# remote_control.net
KiCad netlist of a schematic drawn in EAGLE
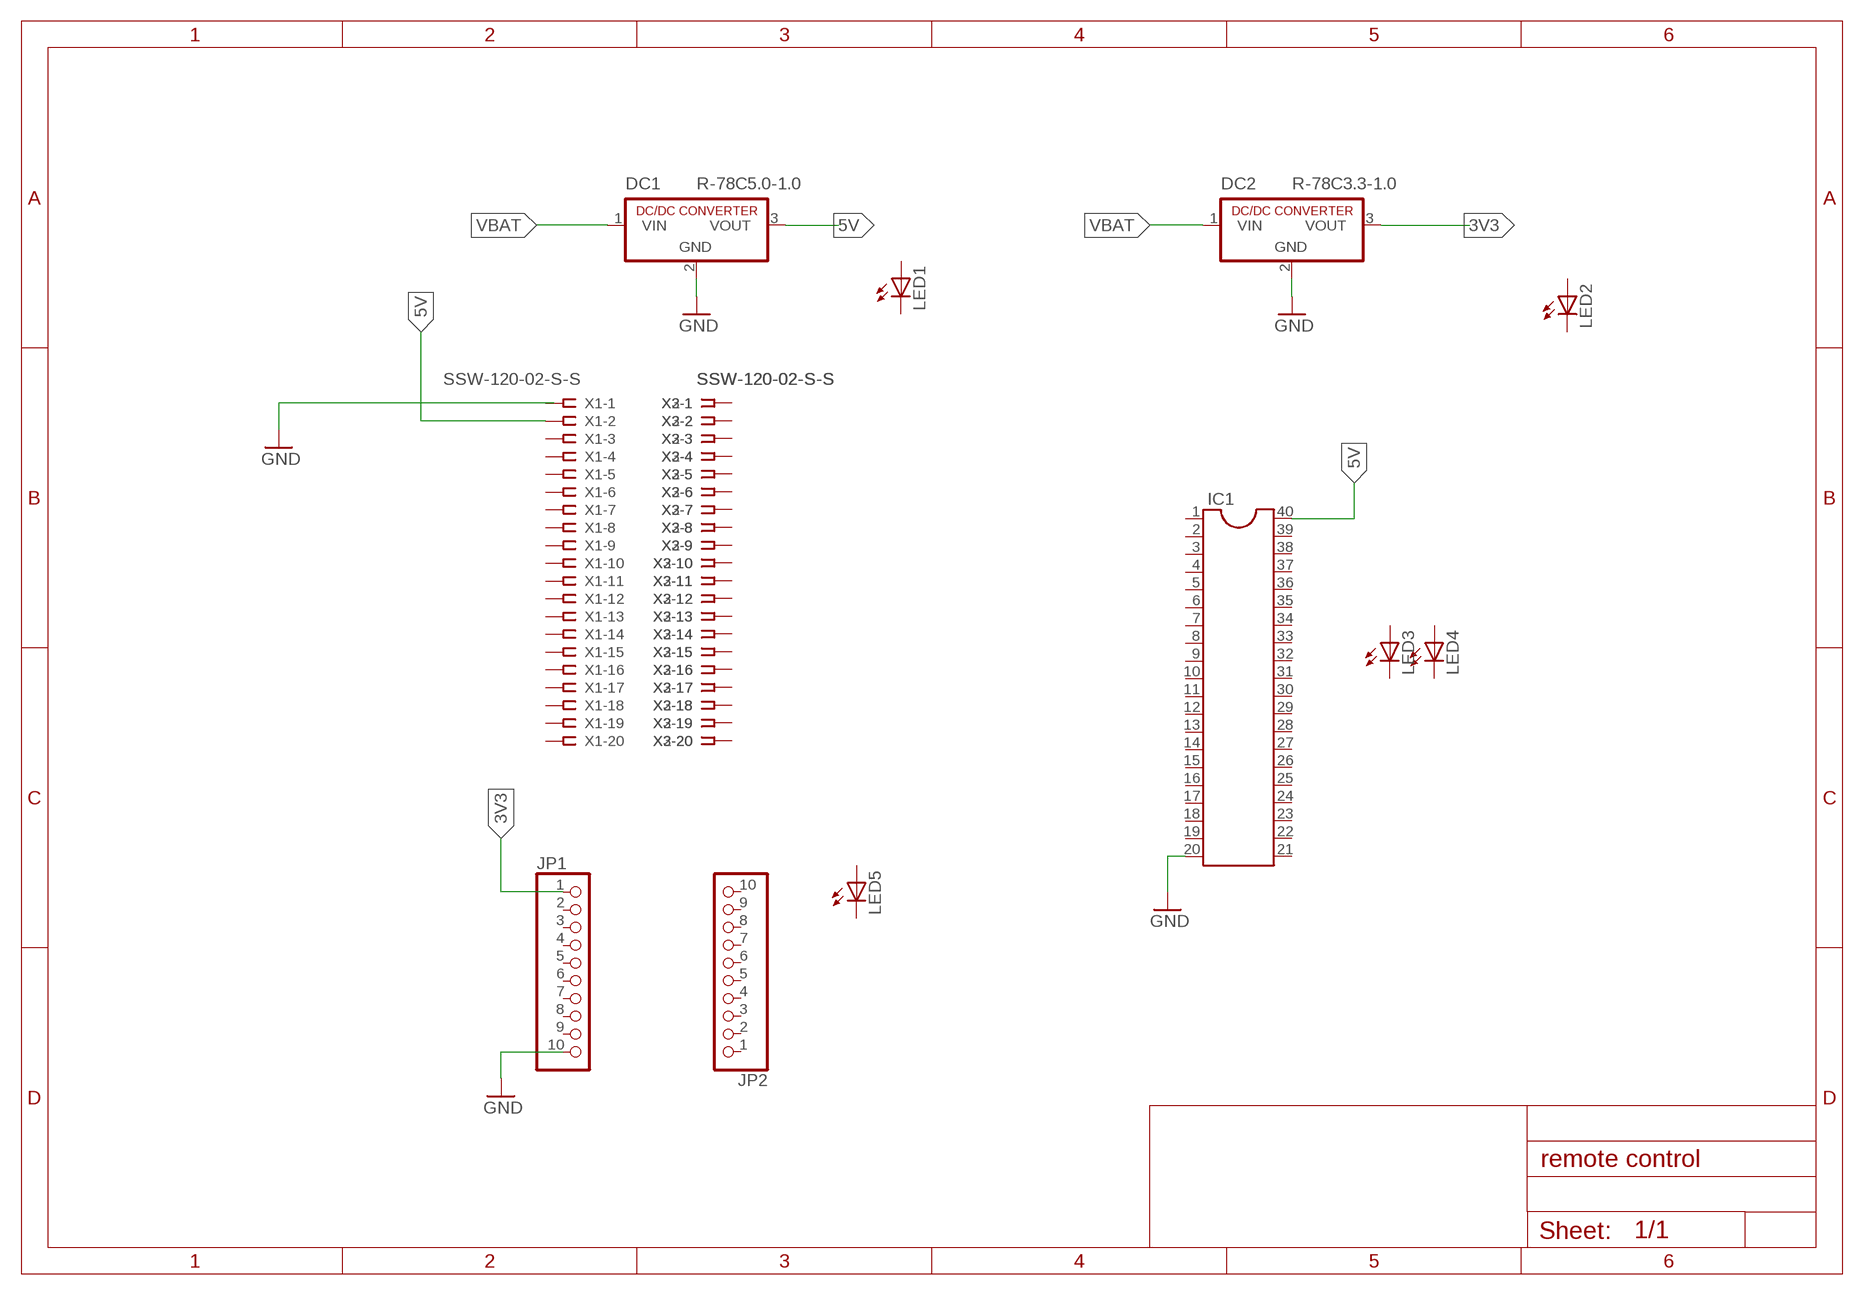
[diagram p0: schematic, sheet 1]

(export (version "E")
  (design (tool "Eeschema 10.0.6"))
  (components
    (comp (ref "DC1")
      (value "R-78C5.0-1.0")
      (footprint "eagle-import:SIP3")
      (libsource (lib "eagle-import") (part "R-78C-1.05.0"))
    )
    (comp (ref "DC2")
      (value "R-78C3.3-1.0")
      (footprint "eagle-import:SIP3")
      (libsource (lib "eagle-import") (part "R-78C-1.03.3"))
    )
    (comp (ref "IC1")
      (value "DIL40")
      (footprint "eagle-import:DIL40")
      (libsource (lib "eagle-import") (part "DIL40"))
    )
    (comp (ref "JP1")
      (value "PINHD-1X10M")
      (footprint "eagle-import:1X10M")
      (libsource (lib "eagle-import") (part "PINHD-1X10M"))
    )
    (comp (ref "JP2")
      (value "PINHD-1X10M")
      (footprint "eagle-import:1X10M")
      (libsource (lib "eagle-import") (part "PINHD-1X10M"))
    )
    (comp (ref "LED1")
      (value "LEDP-LCC-2")
      (footprint "eagle-import:P-LCC-2")
      (libsource (lib "eagle-import") (part "LEDP-LCC-2"))
    )
    (comp (ref "LED2")
      (value "LEDP-LCC-2")
      (footprint "eagle-import:P-LCC-2")
      (libsource (lib "eagle-import") (part "LEDP-LCC-2"))
    )
    (comp (ref "LED3")
      (value "LEDP-LCC-2")
      (footprint "eagle-import:P-LCC-2")
      (libsource (lib "eagle-import") (part "LEDP-LCC-2"))
    )
    (comp (ref "LED4")
      (value "LEDP-LCC-2")
      (footprint "eagle-import:P-LCC-2")
      (libsource (lib "eagle-import") (part "LEDP-LCC-2"))
    )
    (comp (ref "LED5")
      (value "LEDP-LCC-2")
      (footprint "eagle-import:P-LCC-2")
      (libsource (lib "eagle-import") (part "LEDP-LCC-2"))
    )
    (comp (ref "X1")
      (value "SSW-120-02-S-S")
      (footprint "eagle-import:SSW-120-02-S-S")
      (libsource (lib "eagle-import") (part "SSW-120-02-S-S"))
    )
    (comp (ref "X2")
      (value "SSW-120-02-S-S")
      (footprint "eagle-import:SSW-120-02-S-S")
      (libsource (lib "eagle-import") (part "SSW-120-02-S-S"))
    )
    (comp (ref "X3")
      (value "SSW-120-02-S-S")
      (footprint "eagle-import:SSW-120-02-S-S")
      (libsource (lib "eagle-import") (part "SSW-120-02-S-S"))
    )
  )
  (nets
    (net (code "1") (name "3V3") (class "Default")
      (node (ref "DC2") (pin "3") (pinfunction "VOUT_3") (pintype "passive"))
      (node (ref "JP1") (pin "1") (pinfunction "1_1") (pintype "passive"))
    )
    (net (code "2") (name "5V") (class "Default")
      (node (ref "DC1") (pin "3") (pinfunction "VOUT_3") (pintype "passive"))
      (node (ref "IC1") (pin "40") (pinfunction "40_40") (pintype "passive"))
      (node (ref "X1") (pin "2") (pinfunction "1_2") (pintype "passive"))
    )
    (net (code "3") (name "GND") (class "Default")
      (node (ref "DC1") (pin "2") (pinfunction "GND_2") (pintype "passive"))
      (node (ref "DC2") (pin "2") (pinfunction "GND_2") (pintype "passive"))
      (node (ref "IC1") (pin "20") (pinfunction "20_20") (pintype "passive"))
      (node (ref "JP1") (pin "10") (pinfunction "10_10") (pintype "passive"))
    )
    (net (code "4") (name "Net-(X2-Pad1)") (class "Default")
      (node (ref "X2") (pin "1") (pinfunction "1_1") (pintype "passive"))
      (node (ref "X3") (pin "1") (pinfunction "1_1") (pintype "passive"))
    )
    (net (code "5") (name "Net-(X2B-1)") (class "Default")
      (node (ref "X2") (pin "10") (pinfunction "1_10") (pintype "passive"))
      (node (ref "X3") (pin "10") (pinfunction "1_10") (pintype "passive"))
    )
    (net (code "6") (name "Net-(X2C-1)") (class "Default")
      (node (ref "X2") (pin "11") (pinfunction "1_11") (pintype "passive"))
      (node (ref "X3") (pin "11") (pinfunction "1_11") (pintype "passive"))
    )
    (net (code "7") (name "Net-(X2D-1)") (class "Default")
      (node (ref "X2") (pin "12") (pinfunction "1_12") (pintype "passive"))
      (node (ref "X3") (pin "12") (pinfunction "1_12") (pintype "passive"))
    )
    (net (code "8") (name "Net-(X2E-1)") (class "Default")
      (node (ref "X2") (pin "13") (pinfunction "1_13") (pintype "passive"))
      (node (ref "X3") (pin "13") (pinfunction "1_13") (pintype "passive"))
    )
    (net (code "9") (name "Net-(X2F-1)") (class "Default")
      (node (ref "X2") (pin "14") (pinfunction "1_14") (pintype "passive"))
      (node (ref "X3") (pin "14") (pinfunction "1_14") (pintype "passive"))
    )
    (net (code "10") (name "Net-(X2G-1)") (class "Default")
      (node (ref "X2") (pin "15") (pinfunction "1_15") (pintype "passive"))
      (node (ref "X3") (pin "15") (pinfunction "1_15") (pintype "passive"))
    )
    (net (code "11") (name "Net-(X2H-1)") (class "Default")
      (node (ref "X2") (pin "16") (pinfunction "1_16") (pintype "passive"))
      (node (ref "X3") (pin "16") (pinfunction "1_16") (pintype "passive"))
    )
    (net (code "12") (name "Net-(X2I-1)") (class "Default")
      (node (ref "X2") (pin "17") (pinfunction "1_17") (pintype "passive"))
      (node (ref "X3") (pin "17") (pinfunction "1_17") (pintype "passive"))
    )
    (net (code "13") (name "Net-(X2J-1)") (class "Default")
      (node (ref "X2") (pin "18") (pinfunction "1_18") (pintype "passive"))
      (node (ref "X3") (pin "18") (pinfunction "1_18") (pintype "passive"))
    )
    (net (code "14") (name "Net-(X2K-1)") (class "Default")
      (node (ref "X2") (pin "19") (pinfunction "1_19") (pintype "passive"))
      (node (ref "X3") (pin "19") (pinfunction "1_19") (pintype "passive"))
    )
    (net (code "15") (name "Net-(X2L-1)") (class "Default")
      (node (ref "X2") (pin "2") (pinfunction "1_2") (pintype "passive"))
      (node (ref "X3") (pin "2") (pinfunction "1_2") (pintype "passive"))
    )
    (net (code "16") (name "Net-(X2M-1)") (class "Default")
      (node (ref "X2") (pin "20") (pinfunction "1_20") (pintype "passive"))
      (node (ref "X3") (pin "20") (pinfunction "1_20") (pintype "passive"))
    )
    (net (code "17") (name "Net-(X2N-1)") (class "Default")
      (node (ref "X2") (pin "3") (pinfunction "1_3") (pintype "passive"))
      (node (ref "X3") (pin "3") (pinfunction "1_3") (pintype "passive"))
    )
    (net (code "18") (name "Net-(X2O-1)") (class "Default")
      (node (ref "X2") (pin "4") (pinfunction "1_4") (pintype "passive"))
      (node (ref "X3") (pin "4") (pinfunction "1_4") (pintype "passive"))
    )
    (net (code "19") (name "Net-(X2P-1)") (class "Default")
      (node (ref "X2") (pin "5") (pinfunction "1_5") (pintype "passive"))
      (node (ref "X3") (pin "5") (pinfunction "1_5") (pintype "passive"))
    )
    (net (code "20") (name "Net-(X2Q-1)") (class "Default")
      (node (ref "X2") (pin "6") (pinfunction "1_6") (pintype "passive"))
      (node (ref "X3") (pin "6") (pinfunction "1_6") (pintype "passive"))
    )
    (net (code "21") (name "Net-(X2R-1)") (class "Default")
      (node (ref "X2") (pin "7") (pinfunction "1_7") (pintype "passive"))
      (node (ref "X3") (pin "7") (pinfunction "1_7") (pintype "passive"))
    )
    (net (code "22") (name "Net-(X2S-1)") (class "Default")
      (node (ref "X2") (pin "8") (pinfunction "1_8") (pintype "passive"))
      (node (ref "X3") (pin "8") (pinfunction "1_8") (pintype "passive"))
    )
    (net (code "23") (name "Net-(X2T-1)") (class "Default")
      (node (ref "X2") (pin "9") (pinfunction "1_9") (pintype "passive"))
      (node (ref "X3") (pin "9") (pinfunction "1_9") (pintype "passive"))
    )
    (net (code "24") (name "VBAT") (class "Default")
      (node (ref "DC1") (pin "1") (pinfunction "VIN_1") (pintype "passive"))
      (node (ref "DC2") (pin "1") (pinfunction "VIN_1") (pintype "passive"))
    )
    (net (code "25") (name "unconnected-(IC1-Pad1)") (class "Default")
      (node (ref "IC1") (pin "1") (pinfunction "1_1") (pintype "passive"))
    )
    (net (code "26") (name "unconnected-(IC1-Pad2)") (class "Default")
      (node (ref "IC1") (pin "2") (pinfunction "2_2") (pintype "passive"))
    )
    (net (code "27") (name "unconnected-(IC1-Pad3)") (class "Default")
      (node (ref "IC1") (pin "3") (pinfunction "3_3") (pintype "passive"))
    )
    (net (code "28") (name "unconnected-(IC1-Pad4)") (class "Default")
      (node (ref "IC1") (pin "4") (pinfunction "4_4") (pintype "passive"))
    )
    (net (code "29") (name "unconnected-(IC1-Pad5)") (class "Default")
      (node (ref "IC1") (pin "5") (pinfunction "5_5") (pintype "passive"))
    )
    (net (code "30") (name "unconnected-(IC1-Pad6)") (class "Default")
      (node (ref "IC1") (pin "6") (pinfunction "6_6") (pintype "passive"))
    )
    (net (code "31") (name "unconnected-(IC1-Pad7)") (class "Default")
      (node (ref "IC1") (pin "7") (pinfunction "7_7") (pintype "passive"))
    )
    (net (code "32") (name "unconnected-(IC1-Pad8)") (class "Default")
      (node (ref "IC1") (pin "8") (pinfunction "8_8") (pintype "passive"))
    )
    (net (code "33") (name "unconnected-(IC1-Pad9)") (class "Default")
      (node (ref "IC1") (pin "9") (pinfunction "9_9") (pintype "passive"))
    )
    (net (code "34") (name "unconnected-(IC1-Pad10)") (class "Default")
      (node (ref "IC1") (pin "10") (pinfunction "10_10") (pintype "passive"))
    )
    (net (code "35") (name "unconnected-(IC1-Pad11)") (class "Default")
      (node (ref "IC1") (pin "11") (pinfunction "11_11") (pintype "passive"))
    )
    (net (code "36") (name "unconnected-(IC1-Pad12)") (class "Default")
      (node (ref "IC1") (pin "12") (pinfunction "12_12") (pintype "passive"))
    )
    (net (code "37") (name "unconnected-(IC1-Pad13)") (class "Default")
      (node (ref "IC1") (pin "13") (pinfunction "13_13") (pintype "passive"))
    )
    (net (code "38") (name "unconnected-(IC1-Pad14)") (class "Default")
      (node (ref "IC1") (pin "14") (pinfunction "14_14") (pintype "passive"))
    )
    (net (code "39") (name "unconnected-(IC1-Pad15)") (class "Default")
      (node (ref "IC1") (pin "15") (pinfunction "15_15") (pintype "passive"))
    )
    (net (code "40") (name "unconnected-(IC1-Pad16)") (class "Default")
      (node (ref "IC1") (pin "16") (pinfunction "16_16") (pintype "passive"))
    )
    (net (code "41") (name "unconnected-(IC1-Pad17)") (class "Default")
      (node (ref "IC1") (pin "17") (pinfunction "17_17") (pintype "passive"))
    )
    (net (code "42") (name "unconnected-(IC1-Pad18)") (class "Default")
      (node (ref "IC1") (pin "18") (pinfunction "18_18") (pintype "passive"))
    )
    (net (code "43") (name "unconnected-(IC1-Pad19)") (class "Default")
      (node (ref "IC1") (pin "19") (pinfunction "19_19") (pintype "passive"))
    )
    (net (code "44") (name "unconnected-(IC1-Pad21)") (class "Default")
      (node (ref "IC1") (pin "21") (pinfunction "21_21") (pintype "passive"))
    )
    (net (code "45") (name "unconnected-(IC1-Pad22)") (class "Default")
      (node (ref "IC1") (pin "22") (pinfunction "22_22") (pintype "passive"))
    )
    (net (code "46") (name "unconnected-(IC1-Pad23)") (class "Default")
      (node (ref "IC1") (pin "23") (pinfunction "23_23") (pintype "passive"))
    )
    (net (code "47") (name "unconnected-(IC1-Pad24)") (class "Default")
      (node (ref "IC1") (pin "24") (pinfunction "24_24") (pintype "passive"))
    )
    (net (code "48") (name "unconnected-(IC1-Pad25)") (class "Default")
      (node (ref "IC1") (pin "25") (pinfunction "25_25") (pintype "passive"))
    )
    (net (code "49") (name "unconnected-(IC1-Pad26)") (class "Default")
      (node (ref "IC1") (pin "26") (pinfunction "26_26") (pintype "passive"))
    )
    (net (code "50") (name "unconnected-(IC1-Pad27)") (class "Default")
      (node (ref "IC1") (pin "27") (pinfunction "27_27") (pintype "passive"))
    )
    (net (code "51") (name "unconnected-(IC1-Pad28)") (class "Default")
      (node (ref "IC1") (pin "28") (pinfunction "28_28") (pintype "passive"))
    )
    (net (code "52") (name "unconnected-(IC1-Pad29)") (class "Default")
      (node (ref "IC1") (pin "29") (pinfunction "29_29") (pintype "passive"))
    )
    (net (code "53") (name "unconnected-(IC1-Pad30)") (class "Default")
      (node (ref "IC1") (pin "30") (pinfunction "30_30") (pintype "passive"))
    )
    (net (code "54") (name "unconnected-(IC1-Pad31)") (class "Default")
      (node (ref "IC1") (pin "31") (pinfunction "31_31") (pintype "passive"))
    )
    (net (code "55") (name "unconnected-(IC1-Pad32)") (class "Default")
      (node (ref "IC1") (pin "32") (pinfunction "32_32") (pintype "passive"))
    )
    (net (code "56") (name "unconnected-(IC1-Pad33)") (class "Default")
      (node (ref "IC1") (pin "33") (pinfunction "33_33") (pintype "passive"))
    )
    (net (code "57") (name "unconnected-(IC1-Pad34)") (class "Default")
      (node (ref "IC1") (pin "34") (pinfunction "34_34") (pintype "passive"))
    )
    (net (code "58") (name "unconnected-(IC1-Pad35)") (class "Default")
      (node (ref "IC1") (pin "35") (pinfunction "35_35") (pintype "passive"))
    )
    (net (code "59") (name "unconnected-(IC1-Pad36)") (class "Default")
      (node (ref "IC1") (pin "36") (pinfunction "36_36") (pintype "passive"))
    )
    (net (code "60") (name "unconnected-(IC1-Pad37)") (class "Default")
      (node (ref "IC1") (pin "37") (pinfunction "37_37") (pintype "passive"))
    )
    (net (code "61") (name "unconnected-(IC1-Pad38)") (class "Default")
      (node (ref "IC1") (pin "38") (pinfunction "38_38") (pintype "passive"))
    )
    (net (code "62") (name "unconnected-(IC1-Pad39)") (class "Default")
      (node (ref "IC1") (pin "39") (pinfunction "39_39") (pintype "passive"))
    )
    (net (code "63") (name "unconnected-(JP1-Pad2)") (class "Default")
      (node (ref "JP1") (pin "2") (pinfunction "2_2") (pintype "passive"))
    )
    (net (code "64") (name "unconnected-(JP1-Pad3)") (class "Default")
      (node (ref "JP1") (pin "3") (pinfunction "3_3") (pintype "passive"))
    )
    (net (code "65") (name "unconnected-(JP1-Pad4)") (class "Default")
      (node (ref "JP1") (pin "4") (pinfunction "4_4") (pintype "passive"))
    )
    (net (code "66") (name "unconnected-(JP1-Pad5)") (class "Default")
      (node (ref "JP1") (pin "5") (pinfunction "5_5") (pintype "passive"))
    )
    (net (code "67") (name "unconnected-(JP1-Pad6)") (class "Default")
      (node (ref "JP1") (pin "6") (pinfunction "6_6") (pintype "passive"))
    )
    (net (code "68") (name "unconnected-(JP1-Pad7)") (class "Default")
      (node (ref "JP1") (pin "7") (pinfunction "7_7") (pintype "passive"))
    )
    (net (code "69") (name "unconnected-(JP1-Pad8)") (class "Default")
      (node (ref "JP1") (pin "8") (pinfunction "8_8") (pintype "passive"))
    )
    (net (code "70") (name "unconnected-(JP1-Pad9)") (class "Default")
      (node (ref "JP1") (pin "9") (pinfunction "9_9") (pintype "passive"))
    )
    (net (code "71") (name "unconnected-(JP2-Pad1)") (class "Default")
      (node (ref "JP2") (pin "1") (pinfunction "1_1") (pintype "passive"))
    )
    (net (code "72") (name "unconnected-(JP2-Pad2)") (class "Default")
      (node (ref "JP2") (pin "2") (pinfunction "2_2") (pintype "passive"))
    )
    (net (code "73") (name "unconnected-(JP2-Pad3)") (class "Default")
      (node (ref "JP2") (pin "3") (pinfunction "3_3") (pintype "passive"))
    )
    (net (code "74") (name "unconnected-(JP2-Pad4)") (class "Default")
      (node (ref "JP2") (pin "4") (pinfunction "4_4") (pintype "passive"))
    )
    (net (code "75") (name "unconnected-(JP2-Pad5)") (class "Default")
      (node (ref "JP2") (pin "5") (pinfunction "5_5") (pintype "passive"))
    )
    (net (code "76") (name "unconnected-(JP2-Pad6)") (class "Default")
      (node (ref "JP2") (pin "6") (pinfunction "6_6") (pintype "passive"))
    )
    (net (code "77") (name "unconnected-(JP2-Pad7)") (class "Default")
      (node (ref "JP2") (pin "7") (pinfunction "7_7") (pintype "passive"))
    )
    (net (code "78") (name "unconnected-(JP2-Pad8)") (class "Default")
      (node (ref "JP2") (pin "8") (pinfunction "8_8") (pintype "passive"))
    )
    (net (code "79") (name "unconnected-(JP2-Pad9)") (class "Default")
      (node (ref "JP2") (pin "9") (pinfunction "9_9") (pintype "passive"))
    )
    (net (code "80") (name "unconnected-(JP2-Pad10)") (class "Default")
      (node (ref "JP2") (pin "10") (pinfunction "10_10") (pintype "passive"))
    )
    (net (code "81") (name "unconnected-(LED1-PadA)") (class "Default")
      (node (ref "LED1") (pin "A") (pinfunction "A_A") (pintype "passive"))
    )
    (net (code "82") (name "unconnected-(LED1-PadC)") (class "Default")
      (node (ref "LED1") (pin "C") (pinfunction "C_C") (pintype "passive"))
    )
    (net (code "83") (name "unconnected-(LED2-PadA)") (class "Default")
      (node (ref "LED2") (pin "A") (pinfunction "A_A") (pintype "passive"))
    )
    (net (code "84") (name "unconnected-(LED2-PadC)") (class "Default")
      (node (ref "LED2") (pin "C") (pinfunction "C_C") (pintype "passive"))
    )
    (net (code "85") (name "unconnected-(LED3-PadA)") (class "Default")
      (node (ref "LED3") (pin "A") (pinfunction "A_A") (pintype "passive"))
    )
    (net (code "86") (name "unconnected-(LED3-PadC)") (class "Default")
      (node (ref "LED3") (pin "C") (pinfunction "C_C") (pintype "passive"))
    )
    (net (code "87") (name "unconnected-(LED4-PadA)") (class "Default")
      (node (ref "LED4") (pin "A") (pinfunction "A_A") (pintype "passive"))
    )
    (net (code "88") (name "unconnected-(LED4-PadC)") (class "Default")
      (node (ref "LED4") (pin "C") (pinfunction "C_C") (pintype "passive"))
    )
    (net (code "89") (name "unconnected-(LED5-PadA)") (class "Default")
      (node (ref "LED5") (pin "A") (pinfunction "A_A") (pintype "passive"))
    )
    (net (code "90") (name "unconnected-(LED5-PadC)") (class "Default")
      (node (ref "LED5") (pin "C") (pinfunction "C_C") (pintype "passive"))
    )
    (net (code "91") (name "unconnected-(X1-Pad1)") (class "Default")
      (node (ref "X1") (pin "1") (pinfunction "1_1") (pintype "passive"))
    )
    (net (code "92") (name "unconnected-(X1B-1-Pad10)") (class "Default")
      (node (ref "X1") (pin "10") (pinfunction "1_10") (pintype "passive"))
    )
    (net (code "93") (name "unconnected-(X1C-1-Pad11)") (class "Default")
      (node (ref "X1") (pin "11") (pinfunction "1_11") (pintype "passive"))
    )
    (net (code "94") (name "unconnected-(X1D-1-Pad12)") (class "Default")
      (node (ref "X1") (pin "12") (pinfunction "1_12") (pintype "passive"))
    )
    (net (code "95") (name "unconnected-(X1E-1-Pad13)") (class "Default")
      (node (ref "X1") (pin "13") (pinfunction "1_13") (pintype "passive"))
    )
    (net (code "96") (name "unconnected-(X1F-1-Pad14)") (class "Default")
      (node (ref "X1") (pin "14") (pinfunction "1_14") (pintype "passive"))
    )
    (net (code "97") (name "unconnected-(X1G-1-Pad15)") (class "Default")
      (node (ref "X1") (pin "15") (pinfunction "1_15") (pintype "passive"))
    )
    (net (code "98") (name "unconnected-(X1H-1-Pad16)") (class "Default")
      (node (ref "X1") (pin "16") (pinfunction "1_16") (pintype "passive"))
    )
    (net (code "99") (name "unconnected-(X1I-1-Pad17)") (class "Default")
      (node (ref "X1") (pin "17") (pinfunction "1_17") (pintype "passive"))
    )
    (net (code "100") (name "unconnected-(X1J-1-Pad18)") (class "Default")
      (node (ref "X1") (pin "18") (pinfunction "1_18") (pintype "passive"))
    )
    (net (code "101") (name "unconnected-(X1K-1-Pad19)") (class "Default")
      (node (ref "X1") (pin "19") (pinfunction "1_19") (pintype "passive"))
    )
    (net (code "102") (name "unconnected-(X1M-1-Pad20)") (class "Default")
      (node (ref "X1") (pin "20") (pinfunction "1_20") (pintype "passive"))
    )
    (net (code "103") (name "unconnected-(X1N-1-Pad3)") (class "Default")
      (node (ref "X1") (pin "3") (pinfunction "1_3") (pintype "passive"))
    )
    (net (code "104") (name "unconnected-(X1O-1-Pad4)") (class "Default")
      (node (ref "X1") (pin "4") (pinfunction "1_4") (pintype "passive"))
    )
    (net (code "105") (name "unconnected-(X1P-1-Pad5)") (class "Default")
      (node (ref "X1") (pin "5") (pinfunction "1_5") (pintype "passive"))
    )
    (net (code "106") (name "unconnected-(X1Q-1-Pad6)") (class "Default")
      (node (ref "X1") (pin "6") (pinfunction "1_6") (pintype "passive"))
    )
    (net (code "107") (name "unconnected-(X1R-1-Pad7)") (class "Default")
      (node (ref "X1") (pin "7") (pinfunction "1_7") (pintype "passive"))
    )
    (net (code "108") (name "unconnected-(X1S-1-Pad8)") (class "Default")
      (node (ref "X1") (pin "8") (pinfunction "1_8") (pintype "passive"))
    )
    (net (code "109") (name "unconnected-(X1T-1-Pad9)") (class "Default")
      (node (ref "X1") (pin "9") (pinfunction "1_9") (pintype "passive"))
    )
  )
)
